# goldcapplatine.net
KiCad netlist of a schematic drawn in EAGLE
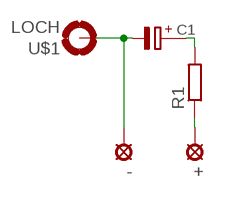
[diagram p0: schematic, sheet 1]

(export (version "E")
  (design (tool "Eeschema 10.0.6"))
  (components
    (comp (ref "+")
      (value "SE11")
      (footprint "eagle-import:SE11")
      (libsource (lib "eagle-import") (part "SE11"))
    )
    (comp (ref "-")
      (value "SE11")
      (footprint "eagle-import:SE11")
      (libsource (lib "eagle-import") (part "SE11"))
    )
    (comp (ref "C1")
      (value "PAC-21,5")
      (footprint "eagle-import:PAC-G-2")
      (libsource (lib "eagle-import") (part "PAC-21,5"))
    )
    (comp (ref "R1")
      (value "R-EU_0207/10")
      (footprint "eagle-import:0207_10")
      (libsource (lib "eagle-import") (part "R-EU_0207/10"))
    )
    (comp (ref "U$1")
      (value "LOCH")
      (footprint "eagle-import:LOCH")
      (libsource (lib "eagle-import") (part "LOCH"))
    )
  )
  (nets
    (net (code "1") (name "Net-(+-PadMP)") (class "Default")
      (node (ref "+") (pin "MP") (pinfunction "MP_MP") (pintype "passive"))
      (node (ref "R1") (pin "1") (pinfunction "1_1") (pintype "passive"))
    )
    (net (code "2") (name "Net-(C1-Pad+)") (class "Default")
      (node (ref "C1") (pin "+") (pinfunction "+_+") (pintype "passive"))
      (node (ref "R1") (pin "2") (pinfunction "2_2") (pintype "passive"))
    )
    (net (code "3") (name "Net-(U$1-MOUNT)") (class "Default")
      (node (ref "-") (pin "MP") (pinfunction "MP_MP") (pintype "passive"))
      (node (ref "C1") (pin "-") (pinfunction "-_-") (pintype "passive"))
      (node (ref "U$1") (pin "B3,0") (pinfunction "MOUNT_B3,0") (pintype "passive"))
    )
  )
)
